# openSX70_MEROE_V7-5_20190606-TSL235.net
KiCad netlist of a schematic drawn in EAGLE
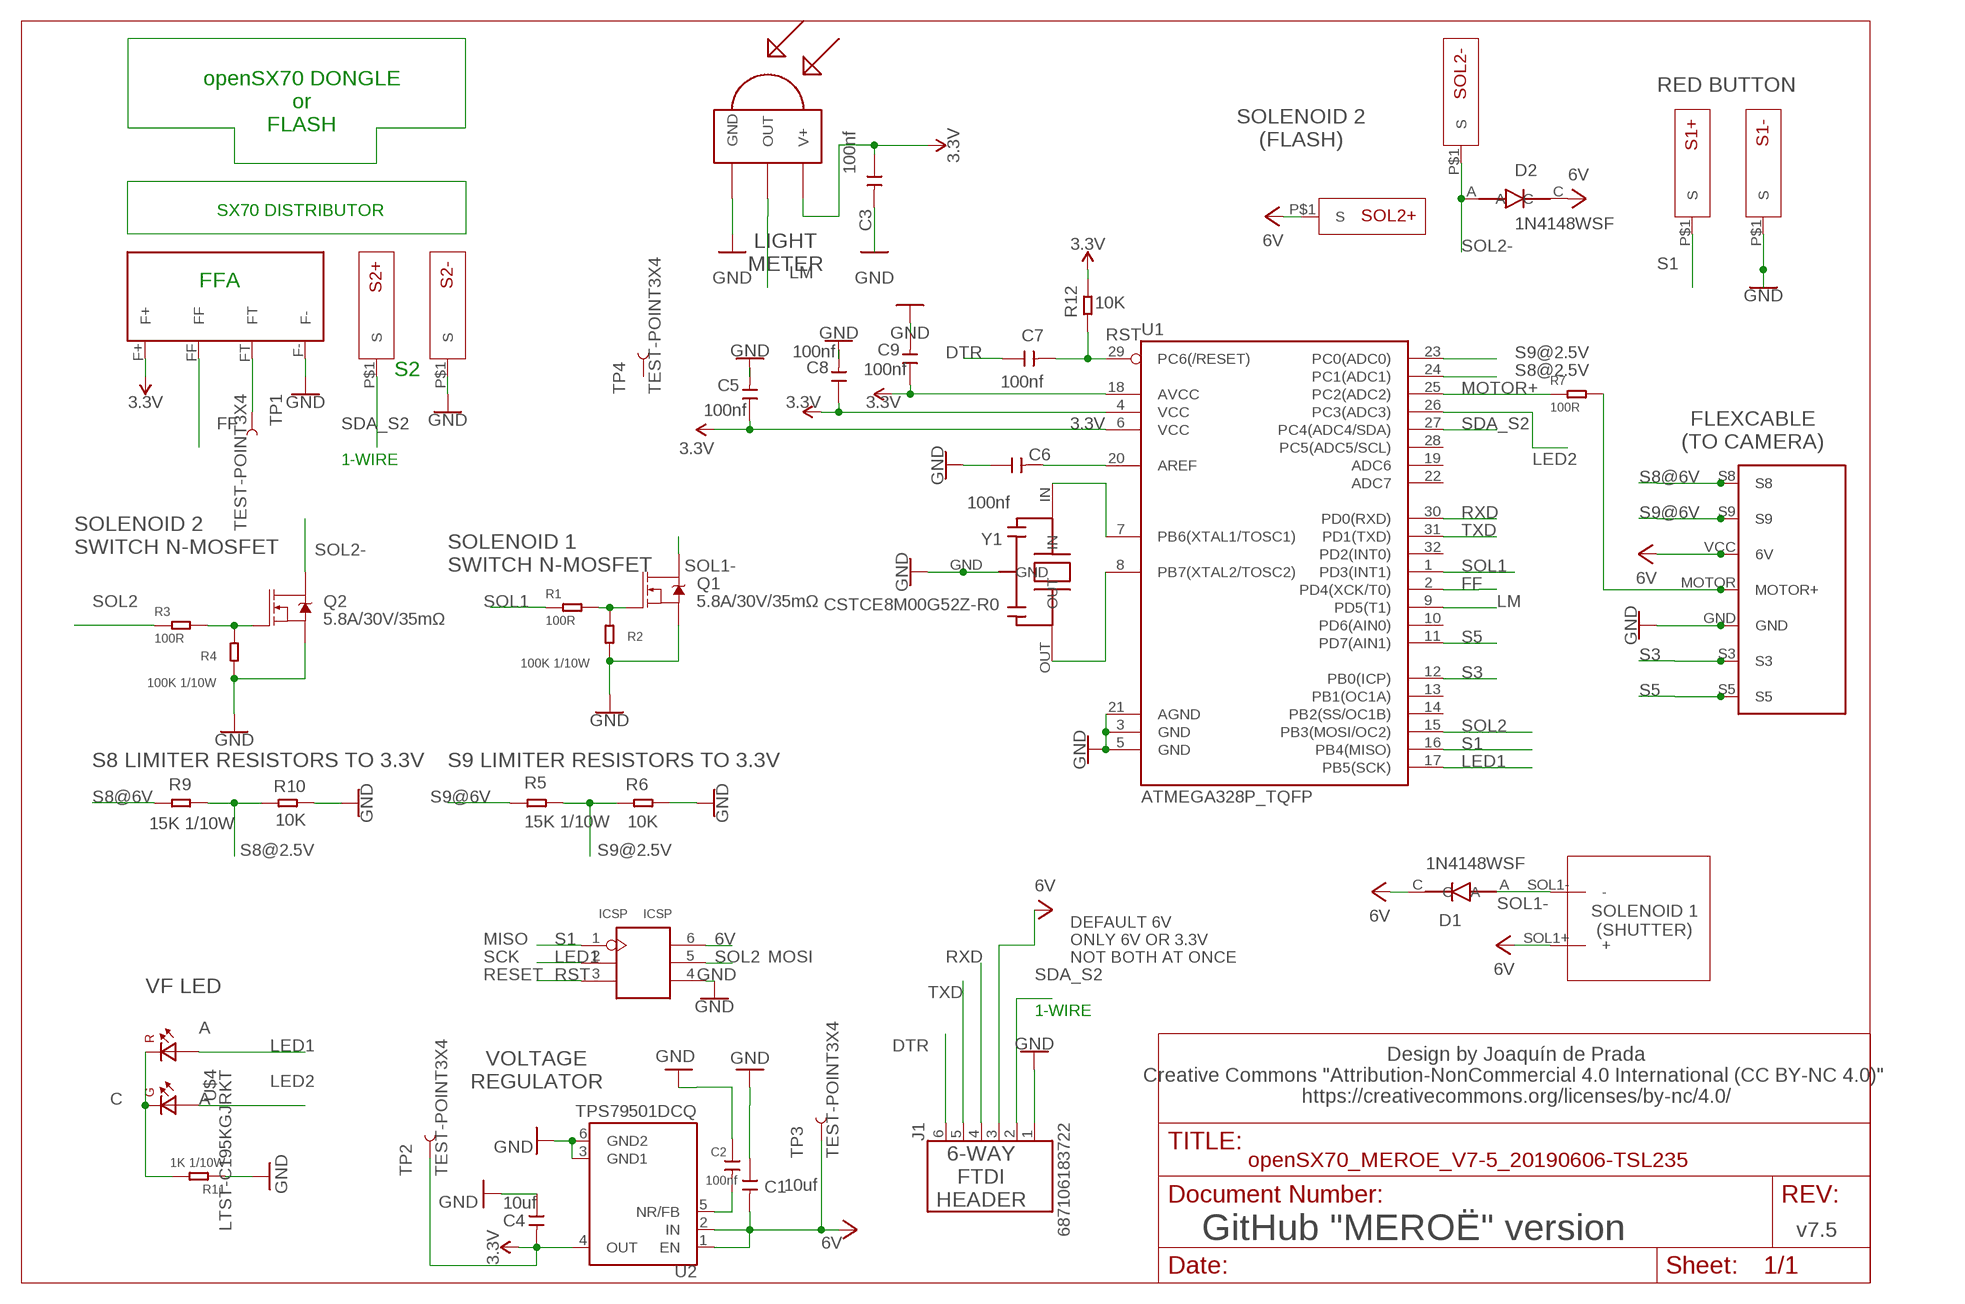
[diagram p0: schematic, sheet 1]

(export (version "E")
  (design (tool "Eeschema 10.0.6"))
  (components
    (comp (ref "C1")
      (value "10uf")
      (footprint "eagle-import:C0603")
      (fields (field (name "MPN") "CC0603KRX5R6BB106"))
      (libsource (lib "eagle-import") (part "CERAMIC-10UF-10V-10%-X5R(0603)"))
    )
    (comp (ref "C2")
      (value "100nf")
      (footprint "eagle-import:C0603")
      (fields (field (name "MPN") "CC0603KRX7R9BB104"))
      (libsource (lib "eagle-import") (part "CERAMIC-100NF-50V-10%-X7R(0603)"))
    )
    (comp (ref "C3")
      (value "100nf")
      (footprint "eagle-import:C0603")
      (fields (field (name "MPN") "CC0603KRX7R9BB104"))
      (libsource (lib "eagle-import") (part "CERAMIC-100NF-50V-10%-X7R(0603)"))
    )
    (comp (ref "C4")
      (value "10uf")
      (footprint "eagle-import:C0603")
      (fields (field (name "MPN") "CC0603KRX5R6BB106"))
      (libsource (lib "eagle-import") (part "CERAMIC-10UF-10V-10%-X5R(0603)"))
    )
    (comp (ref "C5")
      (value "100nf")
      (footprint "eagle-import:C0603")
      (fields (field (name "MPN") "CC0603KRX7R9BB104"))
      (libsource (lib "eagle-import") (part "CERAMIC-100NF-50V-10%-X7R(0603)"))
    )
    (comp (ref "C6")
      (value "100nf")
      (footprint "eagle-import:C0603")
      (fields (field (name "MPN") "CC0603KRX7R9BB104"))
      (libsource (lib "eagle-import") (part "CERAMIC-100NF-50V-10%-X7R(0603)"))
    )
    (comp (ref "C7")
      (value "100nf")
      (footprint "eagle-import:C0603")
      (fields (field (name "MPN") "CC0603KRX7R9BB104"))
      (libsource (lib "eagle-import") (part "CERAMIC-100NF-50V-10%-X7R(0603)"))
    )
    (comp (ref "C8")
      (value "100nf")
      (footprint "eagle-import:C0603")
      (fields (field (name "MPN") "CC0603KRX7R9BB104"))
      (libsource (lib "eagle-import") (part "CERAMIC-100NF-50V-10%-X7R(0603)"))
    )
    (comp (ref "C9")
      (value "100nf")
      (footprint "eagle-import:C0603")
      (fields (field (name "MPN") "CC0603KRX7R9BB104"))
      (libsource (lib "eagle-import") (part "CERAMIC-100NF-50V-10%-X7R(0603)"))
    )
    (comp (ref "D1")
      (value "1N4148WSF")
      (footprint "eagle-import:SODFL2512X100N")
      (fields (field (name "MANUFACTURER") "Fairchild Semiconductor"))
      (libsource (lib "eagle-import") (part "1N4148WS"))
    )
    (comp (ref "D2")
      (value "1N4148WSF")
      (footprint "eagle-import:SODFL2512X100N")
      (fields (field (name "MANUFACTURER") "Fairchild Semiconductor"))
      (libsource (lib "eagle-import") (part "1N4148WS"))
    )
    (comp (ref "ICSP")
      (value "ICSP")
      (footprint "eagle-import:H2X3-2.54")
      (libsource (lib "eagle-import") (part "ICSP"))
    )
    (comp (ref "J1")
      (value "687106183722")
      (footprint "eagle-import:687106183722")
      (fields (field (name "MF") "Wurth Electronics"))
      (libsource (lib "eagle-import") (part "687106183722"))
    )
    (comp (ref "Q1")
      (value "5.8A/30V/35mΩ")
      (footprint "eagle-import:SOT23-3")
      (libsource (lib "eagle-import") (part "MOSFET-NCH-AO3404A"))
    )
    (comp (ref "Q2")
      (value "5.8A/30V/35mΩ")
      (footprint "eagle-import:SOT23-3")
      (libsource (lib "eagle-import") (part "MOSFET-NCH-AO3404A"))
    )
    (comp (ref "R1")
      (value "100R")
      (footprint "eagle-import:R0603")
      (fields (field (name "MPN") "RC0603JR-07100RL"))
      (libsource (lib "eagle-import") (part "SMD-RES-100R-5%-1/10W(0603)"))
    )
    (comp (ref "R2")
      (value "100K 1/10W")
      (footprint "eagle-import:R0603")
      (fields (field (name "MPN") "RC0603JR-07100KL"))
      (libsource (lib "eagle-import") (part "SMD-RES-100K-5%-1/10W(0603)"))
    )
    (comp (ref "R3")
      (value "100R")
      (footprint "eagle-import:R0603")
      (fields (field (name "MPN") "RC0603JR-07100RL"))
      (libsource (lib "eagle-import") (part "SMD-RES-100R-5%-1/10W(0603)"))
    )
    (comp (ref "R4")
      (value "100K 1/10W")
      (footprint "eagle-import:R0603")
      (fields (field (name "MPN") "RC0603JR-07100KL"))
      (libsource (lib "eagle-import") (part "SMD-RES-100K-5%-1/10W(0603)"))
    )
    (comp (ref "R5")
      (value "15K 1/10W")
      (footprint "eagle-import:R0603")
      (fields (field (name "MPN") "RC0603FR-0715KL"))
      (libsource (lib "eagle-import") (part "SMD-RES-15K-1%-1/10W(0603)"))
    )
    (comp (ref "R6")
      (value "10K")
      (footprint "eagle-import:R0603")
      (fields (field (name "MPN") "RC0603FR-0710KL"))
      (libsource (lib "eagle-import") (part "SMD-RES-10K-1%-1/10W(0603)"))
    )
    (comp (ref "R7")
      (value "100R")
      (footprint "eagle-import:R0603")
      (fields (field (name "MPN") "RC0603JR-07100RL"))
      (libsource (lib "eagle-import") (part "SMD-RES-100R-5%-1/10W(0603)"))
    )
    (comp (ref "R9")
      (value "15K 1/10W")
      (footprint "eagle-import:R0603")
      (fields (field (name "MPN") "RC0603FR-0715KL"))
      (libsource (lib "eagle-import") (part "SMD-RES-15K-1%-1/10W(0603)"))
    )
    (comp (ref "R10")
      (value "10K")
      (footprint "eagle-import:R0603")
      (fields (field (name "MPN") "RC0603FR-0710KL"))
      (libsource (lib "eagle-import") (part "SMD-RES-10K-1%-1/10W(0603)"))
    )
    (comp (ref "R11")
      (value "1K 1/10W")
      (footprint "eagle-import:R0603")
      (fields (field (name "MPN") "RC0603JR-071KL"))
      (libsource (lib "eagle-import") (part "SMD-RES-1K-5%-1/10W(0603)"))
    )
    (comp (ref "R12")
      (value "10K")
      (footprint "eagle-import:R0603")
      (fields (field (name "MPN") "RC0603FR-0710KL"))
      (libsource (lib "eagle-import") (part "SMD-RES-10K-1%-1/10W(0603)"))
    )
    (comp (ref "S1+")
      (value "SX70-S-PAD-NEW")
      (footprint "eagle-import:SX70-S-PAD2")
      (libsource (lib "eagle-import") (part "SX70-S-PAD-NEW"))
    )
    (comp (ref "S1-")
      (value "SX70-S-PAD-NEW")
      (footprint "eagle-import:SX70-S-PAD2")
      (libsource (lib "eagle-import") (part "SX70-S-PAD-NEW"))
    )
    (comp (ref "S2+")
      (value "SX70-S-PAD-NEW")
      (footprint "eagle-import:SX70-S-PAD2")
      (libsource (lib "eagle-import") (part "SX70-S-PAD-NEW"))
    )
    (comp (ref "S2-")
      (value "SX70-S-PAD-NEW")
      (footprint "eagle-import:SX70-S-PAD2")
      (libsource (lib "eagle-import") (part "SX70-S-PAD-NEW"))
    )
    (comp (ref "SOL1")
      (value "SX70-SOLENOID1-2PADS")
      (footprint "eagle-import:SX70-SOLENOID1-2")
      (libsource (lib "eagle-import") (part "SX70-SOLENOID1-2PADS"))
    )
    (comp (ref "SOL2+")
      (value "SX70-S-PAD-NEW")
      (footprint "eagle-import:SX70-S-PAD2")
      (libsource (lib "eagle-import") (part "SX70-S-PAD-NEW"))
    )
    (comp (ref "SOL2-")
      (value "SX70-S-PAD-NEW")
      (footprint "eagle-import:SX70-S-PAD2")
      (libsource (lib "eagle-import") (part "SX70-S-PAD-NEW"))
    )
    (comp (ref "TP1")
      (value "TEST-POINT3X4")
      (footprint "eagle-import:PAD.03X.04")
      (libsource (lib "eagle-import") (part "TEST-POINT3X4"))
    )
    (comp (ref "TP2")
      (value "TEST-POINT3X4")
      (footprint "eagle-import:PAD.03X.04")
      (libsource (lib "eagle-import") (part "TEST-POINT3X4"))
    )
    (comp (ref "TP3")
      (value "TEST-POINT3X4")
      (footprint "eagle-import:PAD.03X.04")
      (libsource (lib "eagle-import") (part "TEST-POINT3X4"))
    )
    (comp (ref "TP4")
      (value "TEST-POINT3X4")
      (footprint "eagle-import:PAD.03X.04")
      (libsource (lib "eagle-import") (part "TEST-POINT3X4"))
    )
    (comp (ref "U$1")
      (value "SX70-7-PAD")
      (footprint "eagle-import:SX70-7-PAD-PROPER")
      (libsource (lib "eagle-import") (part "SX70-7-PAD"))
    )
    (comp (ref "U$2")
      (value "FFA")
      (footprint "eagle-import:FFA-PAD-PACKAGE")
      (libsource (lib "eagle-import") (part "SX70-FFA-PAD"))
    )
    (comp (ref "U$3")
      (value "TSL235R")
      (footprint "eagle-import:TSL235R")
      (libsource (lib "eagle-import") (part "TSL235R"))
    )
    (comp (ref "U$4")
      (value "LTST-C195KGJRKT")
      (footprint "eagle-import:LTST-BILED-15X16")
      (fields (field (name "MF") "Lite-On Inc."))
      (libsource (lib "eagle-import") (part "LTST-C195KGJRKT"))
    )
    (comp (ref "U1")
      (value "ATMEGA328P_TQFP")
      (footprint "eagle-import:TQFP32-08")
      (libsource (lib "eagle-import") (part "ATMEGA328P_TQFP"))
    )
    (comp (ref "U2")
      (value "TPS79501DCQ")
      (footprint "eagle-import:SOT127P706X180-6N")
      (fields (field (name "DIGI-KEY_PART_NUMBER") "296-27102-5-ND") (field (name "MF") "Texas Instruments"))
      (libsource (lib "eagle-import") (part "TPS79501DCQ"))
    )
    (comp (ref "Y1")
      (value "CSTCE8M00G52Z-R0")
      (footprint "eagle-import:CFP95P160X100-3N")
      (fields (field (name "MF") "Murata") (field (name "MP") "CSTCE16M0V53-R0"))
      (libsource (lib "eagle-import") (part "CSTCE16M0V53-R0"))
    )
  )
  (nets
    (net (code "1") (name "/DTR") (class "Default")
      (node (ref "C7") (pin "1") (pinfunction "1_1") (pintype "passive"))
      (node (ref "J1") (pin "6") (pinfunction "1_6") (pintype "passive"))
    )
    (net (code "2") (name "/FF") (class "Default")
      (node (ref "U$2") (pin "FF") (pinfunction "FF_FF") (pintype "bidirectional"))
      (node (ref "U1") (pin "2") (pinfunction "PD4(XCK/T0)_2") (pintype "bidirectional"))
    )
    (net (code "3") (name "/LED1") (class "Default")
      (node (ref "ICSP") (pin "2") (pinfunction "SCK_2") (pintype "bidirectional"))
      (node (ref "U$4") (pin "P$2") (pinfunction "A2_P$2") (pintype "passive"))
      (node (ref "U1") (pin "17") (pinfunction "PB5(SCK)_17") (pintype "bidirectional"))
    )
    (net (code "4") (name "/LED2") (class "Default")
      (node (ref "U$4") (pin "P$1") (pinfunction "A1_P$1") (pintype "passive"))
      (node (ref "U1") (pin "26") (pinfunction "PC3(ADC3)_26") (pintype "bidirectional"))
    )
    (net (code "5") (name "/LM") (class "Default")
      (node (ref "U$3") (pin "OUT") (pinfunction "OUT_OUT") (pintype "bidirectional"))
      (node (ref "U1") (pin "9") (pinfunction "PD5(T1)_9") (pintype "bidirectional"))
    )
    (net (code "6") (name "/MOTOR+") (class "Default")
      (node (ref "R7") (pin "1") (pinfunction "1_1") (pintype "passive"))
      (node (ref "U1") (pin "25") (pinfunction "PC2(ADC2)_25") (pintype "bidirectional"))
    )
    (net (code "7") (name "/RST") (class "Default")
      (node (ref "C7") (pin "2") (pinfunction "2_2") (pintype "passive"))
      (node (ref "ICSP") (pin "3") (pinfunction "RST_3") (pintype "bidirectional"))
      (node (ref "R12") (pin "1") (pinfunction "1_1") (pintype "passive"))
      (node (ref "U1") (pin "29") (pinfunction "PC6(/RESET)_29") (pintype "bidirectional"))
    )
    (net (code "8") (name "/RXD") (class "Default")
      (node (ref "J1") (pin "4") (pinfunction "3_4") (pintype "passive"))
      (node (ref "U1") (pin "30") (pinfunction "PD0(RXD)_30") (pintype "bidirectional"))
    )
    (net (code "9") (name "/S1") (class "Default")
      (node (ref "ICSP") (pin "1") (pinfunction "MISO_1") (pintype "bidirectional"))
      (node (ref "S1+") (pin "P$1") (pinfunction "S_P$1") (pintype "bidirectional"))
      (node (ref "U1") (pin "16") (pinfunction "PB4(MISO)_16") (pintype "bidirectional"))
    )
    (net (code "10") (name "/S3") (class "Default")
      (node (ref "U$1") (pin "S3") (pinfunction "S3_S3") (pintype "bidirectional"))
      (node (ref "U1") (pin "12") (pinfunction "PB0(ICP)_12") (pintype "bidirectional"))
    )
    (net (code "11") (name "/S5") (class "Default")
      (node (ref "U$1") (pin "S5") (pinfunction "S5_S5") (pintype "bidirectional"))
      (node (ref "U1") (pin "11") (pinfunction "PD7(AIN1)_11") (pintype "bidirectional"))
    )
    (net (code "12") (name "/S8@2.5V") (class "Default")
      (node (ref "R10") (pin "1") (pinfunction "1_1") (pintype "passive"))
      (node (ref "R9") (pin "2") (pinfunction "2_2") (pintype "passive"))
      (node (ref "U1") (pin "24") (pinfunction "PC1(ADC1)_24") (pintype "bidirectional"))
    )
    (net (code "13") (name "/S8@6V") (class "Default")
      (node (ref "R9") (pin "1") (pinfunction "1_1") (pintype "passive"))
      (node (ref "U$1") (pin "S8") (pinfunction "S8_S8") (pintype "bidirectional"))
    )
    (net (code "14") (name "/S9@2.5V") (class "Default")
      (node (ref "R5") (pin "2") (pinfunction "2_2") (pintype "passive"))
      (node (ref "R6") (pin "1") (pinfunction "1_1") (pintype "passive"))
      (node (ref "U1") (pin "23") (pinfunction "PC0(ADC0)_23") (pintype "bidirectional"))
    )
    (net (code "15") (name "/S9@6V") (class "Default")
      (node (ref "R5") (pin "1") (pinfunction "1_1") (pintype "passive"))
      (node (ref "U$1") (pin "S9") (pinfunction "S9_S9") (pintype "bidirectional"))
    )
    (net (code "16") (name "/SDA_S2") (class "Default")
      (node (ref "J1") (pin "2") (pinfunction "5_2") (pintype "passive"))
      (node (ref "S2+") (pin "P$1") (pinfunction "S_P$1") (pintype "bidirectional"))
      (node (ref "U1") (pin "27") (pinfunction "PC4(ADC4/SDA)_27") (pintype "bidirectional"))
    )
    (net (code "17") (name "/SOL1") (class "Default")
      (node (ref "R1") (pin "1") (pinfunction "1_1") (pintype "passive"))
      (node (ref "U1") (pin "1") (pinfunction "PD3(INT1)_1") (pintype "bidirectional"))
    )
    (net (code "18") (name "/SOL1-") (class "Default")
      (node (ref "D1") (pin "A") (pinfunction "A_A") (pintype "passive"))
      (node (ref "Q1") (pin "3") (pinfunction "D_3") (pintype "bidirectional"))
      (node (ref "SOL1") (pin "SOL1-") (pinfunction "-_SOL1-") (pintype "bidirectional"))
    )
    (net (code "19") (name "/SOL2") (class "Default")
      (node (ref "ICSP") (pin "5") (pinfunction "MOSI_5") (pintype "bidirectional"))
      (node (ref "R3") (pin "1") (pinfunction "1_1") (pintype "passive"))
      (node (ref "U1") (pin "15") (pinfunction "PB3(MOSI/OC2)_15") (pintype "bidirectional"))
    )
    (net (code "20") (name "/SOL2-") (class "Default")
      (node (ref "D2") (pin "A") (pinfunction "A_A") (pintype "passive"))
      (node (ref "Q2") (pin "3") (pinfunction "D_3") (pintype "bidirectional"))
      (node (ref "SOL2-") (pin "P$1") (pinfunction "S_P$1") (pintype "bidirectional"))
    )
    (net (code "21") (name "/TXD") (class "Default")
      (node (ref "J1") (pin "5") (pinfunction "2_5") (pintype "passive"))
      (node (ref "U1") (pin "31") (pinfunction "PD1(TXD)_31") (pintype "bidirectional"))
    )
    (net (code "22") (name "3.3V") (class "Default")
      (node (ref "C3") (pin "1") (pinfunction "1_1") (pintype "passive"))
      (node (ref "C4") (pin "2") (pinfunction "2_2") (pintype "passive"))
      (node (ref "C5") (pin "1") (pinfunction "1_1") (pintype "passive"))
      (node (ref "C8") (pin "1") (pinfunction "1_1") (pintype "passive"))
      (node (ref "C9") (pin "1") (pinfunction "1_1") (pintype "passive"))
      (node (ref "R12") (pin "2") (pinfunction "2_2") (pintype "passive"))
      (node (ref "TP2") (pin "P$1") (pinfunction "1_P$1") (pintype "bidirectional"))
      (node (ref "U$2") (pin "F+") (pinfunction "F+_F+") (pintype "bidirectional"))
      (node (ref "U$3") (pin "VDD") (pinfunction "V+_VDD") (pintype "bidirectional"))
      (node (ref "U1") (pin "18") (pinfunction "AVCC_18") (pintype "bidirectional"))
      (node (ref "U1") (pin "4") (pinfunction "VCC_4") (pintype "bidirectional"))
      (node (ref "U1") (pin "6") (pinfunction "VCC_6") (pintype "bidirectional"))
      (node (ref "U2") (pin "4") (pinfunction "OUT_4") (pintype "output"))
    )
    (net (code "23") (name "6V") (class "Default")
      (node (ref "C1") (pin "2") (pinfunction "2_2") (pintype "passive"))
      (node (ref "D1") (pin "C") (pinfunction "C_C") (pintype "passive"))
      (node (ref "D2") (pin "C") (pinfunction "C_C") (pintype "passive"))
      (node (ref "ICSP") (pin "6") (pinfunction "VCC_6") (pintype "bidirectional"))
      (node (ref "J1") (pin "3") (pinfunction "4_3") (pintype "passive"))
      (node (ref "SOL1") (pin "SOL1+") (pinfunction "+_SOL1+") (pintype "bidirectional"))
      (node (ref "SOL2+") (pin "P$1") (pinfunction "S_P$1") (pintype "bidirectional"))
      (node (ref "TP3") (pin "P$1") (pinfunction "1_P$1") (pintype "bidirectional"))
      (node (ref "U$1") (pin "VCC") (pinfunction "6V_VCC") (pintype "bidirectional"))
      (node (ref "U2") (pin "1") (pinfunction "EN_1") (pintype "input"))
      (node (ref "U2") (pin "2") (pinfunction "IN_2") (pintype "input"))
    )
    (net (code "24") (name "GND") (class "Default")
      (node (ref "C1") (pin "1") (pinfunction "1_1") (pintype "passive"))
      (node (ref "C2") (pin "1") (pinfunction "1_1") (pintype "passive"))
      (node (ref "C3") (pin "2") (pinfunction "2_2") (pintype "passive"))
      (node (ref "C4") (pin "1") (pinfunction "1_1") (pintype "passive"))
      (node (ref "C5") (pin "2") (pinfunction "2_2") (pintype "passive"))
      (node (ref "C6") (pin "1") (pinfunction "1_1") (pintype "passive"))
      (node (ref "C8") (pin "2") (pinfunction "2_2") (pintype "passive"))
      (node (ref "C9") (pin "2") (pinfunction "2_2") (pintype "passive"))
      (node (ref "ICSP") (pin "4") (pinfunction "GND_4") (pintype "bidirectional"))
      (node (ref "J1") (pin "1") (pinfunction "6_1") (pintype "passive"))
      (node (ref "Q1") (pin "2") (pinfunction "S_2") (pintype "bidirectional"))
      (node (ref "Q2") (pin "2") (pinfunction "S_2") (pintype "bidirectional"))
      (node (ref "R10") (pin "2") (pinfunction "2_2") (pintype "passive"))
      (node (ref "R11") (pin "1") (pinfunction "1_1") (pintype "passive"))
      (node (ref "R2") (pin "1") (pinfunction "1_1") (pintype "passive"))
      (node (ref "R4") (pin "1") (pinfunction "1_1") (pintype "passive"))
      (node (ref "R6") (pin "2") (pinfunction "2_2") (pintype "passive"))
      (node (ref "S1-") (pin "P$1") (pinfunction "S_P$1") (pintype "bidirectional"))
      (node (ref "S2-") (pin "P$1") (pinfunction "S_P$1") (pintype "bidirectional"))
      (node (ref "U$1") (pin "GND") (pinfunction "GND_GND") (pintype "bidirectional"))
      (node (ref "U$2") (pin "F-") (pinfunction "F-_F-") (pintype "bidirectional"))
      (node (ref "U$3") (pin "GND") (pinfunction "GND_GND") (pintype "bidirectional"))
      (node (ref "U1") (pin "21") (pinfunction "AGND_21") (pintype "bidirectional"))
      (node (ref "U1") (pin "3") (pinfunction "GND_3") (pintype "bidirectional"))
      (node (ref "U1") (pin "5") (pinfunction "GND_5") (pintype "bidirectional"))
      (node (ref "U2") (pin "3") (pinfunction "GND1_3") (pintype "power_in"))
      (node (ref "U2") (pin "6") (pinfunction "GND2_6") (pintype "power_in"))
      (node (ref "Y1") (pin "GND") (pinfunction "GND_GND") (pintype "passive"))
    )
    (net (code "25") (name "Net-(Q1-G)") (class "Default")
      (node (ref "Q1") (pin "1") (pinfunction "G_1") (pintype "bidirectional"))
      (node (ref "R1") (pin "2") (pinfunction "2_2") (pintype "passive"))
      (node (ref "R2") (pin "2") (pinfunction "2_2") (pintype "passive"))
    )
    (net (code "26") (name "Net-(Q2-G)") (class "Default")
      (node (ref "Q2") (pin "1") (pinfunction "G_1") (pintype "bidirectional"))
      (node (ref "R3") (pin "2") (pinfunction "2_2") (pintype "passive"))
      (node (ref "R4") (pin "2") (pinfunction "2_2") (pintype "passive"))
    )
    (net (code "27") (name "Net-(TP1-1)") (class "Default")
      (node (ref "TP1") (pin "P$1") (pinfunction "1_P$1") (pintype "bidirectional"))
      (node (ref "U$2") (pin "FT") (pinfunction "FT_FT") (pintype "bidirectional"))
    )
    (net (code "28") (name "Net-(U$1-MOTOR+)") (class "Default")
      (node (ref "R7") (pin "2") (pinfunction "2_2") (pintype "passive"))
      (node (ref "U$1") (pin "MOTOR") (pinfunction "MOTOR+_MOTOR") (pintype "bidirectional"))
    )
    (net (code "29") (name "Net-(U$4-K1)") (class "Default")
      (node (ref "R11") (pin "2") (pinfunction "2_2") (pintype "passive"))
      (node (ref "U$4") (pin "P$3") (pinfunction "K1_P$3") (pintype "passive"))
      (node (ref "U$4") (pin "P$4") (pinfunction "K2_P$4") (pintype "passive"))
    )
    (net (code "30") (name "Net-(U1-AREF)") (class "Default")
      (node (ref "C6") (pin "2") (pinfunction "2_2") (pintype "passive"))
      (node (ref "U1") (pin "20") (pinfunction "AREF_20") (pintype "bidirectional"))
    )
    (net (code "31") (name "Net-(U1-PB6(XTAL1{slash}TOSC1))") (class "Default")
      (node (ref "U1") (pin "7") (pinfunction "PB6(XTAL1/TOSC1)_7") (pintype "bidirectional"))
      (node (ref "Y1") (pin "IN") (pinfunction "IN_IN") (pintype "input"))
    )
    (net (code "32") (name "Net-(U1-PB7(XTAL2{slash}TOSC2))") (class "Default")
      (node (ref "U1") (pin "8") (pinfunction "PB7(XTAL2/TOSC2)_8") (pintype "bidirectional"))
      (node (ref "Y1") (pin "OUT") (pinfunction "OUT_OUT") (pintype "output"))
    )
    (net (code "33") (name "Net-(U2-NR{slash}FB)") (class "Default")
      (node (ref "C2") (pin "2") (pinfunction "2_2") (pintype "passive"))
      (node (ref "U2") (pin "5") (pinfunction "NR/FB_5") (pintype "input"))
    )
    (net (code "34") (name "unconnected-(TP4-1-PadP$1)") (class "Default")
      (node (ref "TP4") (pin "P$1") (pinfunction "1_P$1") (pintype "bidirectional"))
    )
    (net (code "35") (name "unconnected-(U1-ADC6-Pad19)") (class "Default")
      (node (ref "U1") (pin "19") (pinfunction "ADC6_19") (pintype "bidirectional"))
    )
    (net (code "36") (name "unconnected-(U1-ADC7-Pad22)") (class "Default")
      (node (ref "U1") (pin "22") (pinfunction "ADC7_22") (pintype "bidirectional"))
    )
    (net (code "37") (name "unconnected-(U1-PB1(OC1A)-Pad13)") (class "Default")
      (node (ref "U1") (pin "13") (pinfunction "PB1(OC1A)_13") (pintype "bidirectional"))
    )
    (net (code "38") (name "unconnected-(U1-PB2(SS{slash}OC1B)-Pad14)") (class "Default")
      (node (ref "U1") (pin "14") (pinfunction "PB2(SS/OC1B)_14") (pintype "bidirectional"))
    )
    (net (code "39") (name "unconnected-(U1-PC5(ADC5{slash}SCL)-Pad28)") (class "Default")
      (node (ref "U1") (pin "28") (pinfunction "PC5(ADC5/SCL)_28") (pintype "bidirectional"))
    )
    (net (code "40") (name "unconnected-(U1-PD2(INT0)-Pad32)") (class "Default")
      (node (ref "U1") (pin "32") (pinfunction "PD2(INT0)_32") (pintype "bidirectional"))
    )
    (net (code "41") (name "unconnected-(U1-PD6(AIN0)-Pad10)") (class "Default")
      (node (ref "U1") (pin "10") (pinfunction "PD6(AIN0)_10") (pintype "bidirectional"))
    )
  )
)
